# xbee_adapter.net
KiCad netlist of a schematic drawn in EAGLE
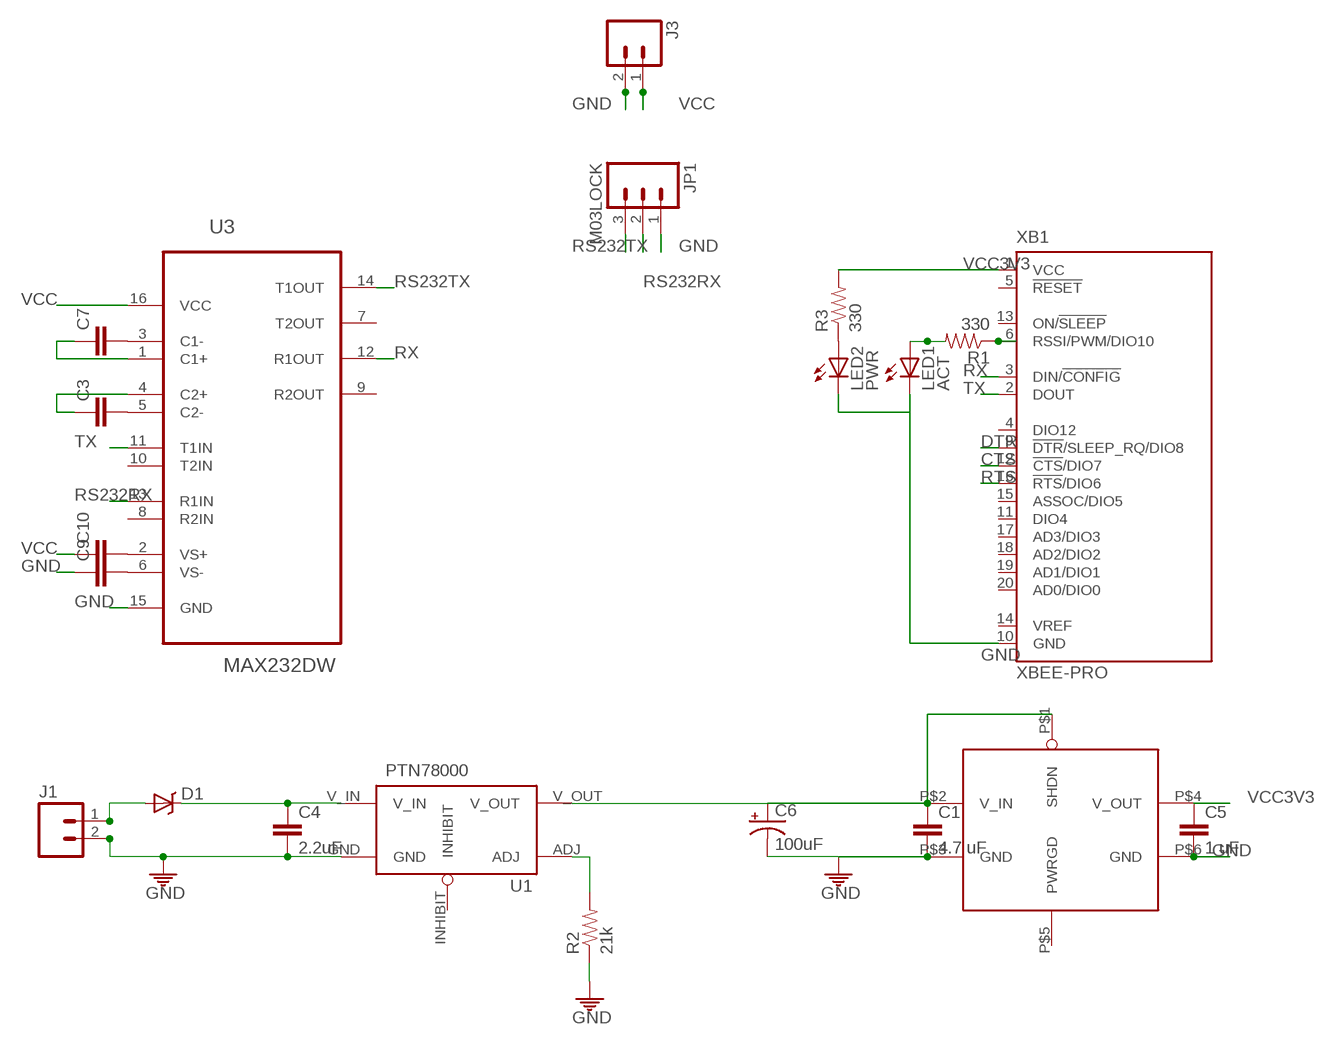
[diagram p0: schematic, sheet 1]

(export (version "E")
  (design (tool "Eeschema 10.0.6"))
  (components
    (comp (ref "C1")
      (value "4.7 uF")
      (footprint "eagle-import:1206")
      (libsource (lib "eagle-import") (part "CAP1206"))
    )
    (comp (ref "C3")
      (value "CAP1206")
      (footprint "eagle-import:1206")
      (libsource (lib "eagle-import") (part "CAP1206"))
    )
    (comp (ref "C4")
      (value "2.2uF")
      (footprint "eagle-import:1206")
      (libsource (lib "eagle-import") (part "CMPE118lib_CAP1206"))
    )
    (comp (ref "C5")
      (value "1 uF")
      (footprint "eagle-import:1206")
      (libsource (lib "eagle-import") (part "CAP1206"))
    )
    (comp (ref "C6")
      (value "100uF")
      (footprint "eagle-import:CPOL_6.6")
      (libsource (lib "eagle-import") (part "CAP_POL"))
    )
    (comp (ref "C7")
      (value "CAP1206")
      (footprint "eagle-import:1206")
      (libsource (lib "eagle-import") (part "CAP1206"))
    )
    (comp (ref "C9")
      (value "CAP1206")
      (footprint "eagle-import:1206")
      (libsource (lib "eagle-import") (part "CAP1206"))
    )
    (comp (ref "C10")
      (value "CAP1206")
      (footprint "eagle-import:1206")
      (libsource (lib "eagle-import") (part "CAP1206"))
    )
    (comp (ref "D1")
      (value "DIODE-SCHOTTKY240A")
      (footprint "eagle-import:SMA-DIODE-B240A")
      (libsource (lib "eagle-import") (part "DIODE-SCHOTTKY240A"))
    )
    (comp (ref "J1")
      (value "M023.5MM-NO_SILK")
      (footprint "eagle-import:SCREWTERMINAL-3.5MM-2-NS")
      (libsource (lib "eagle-import") (part "M023.5MM-NO_SILK"))
    )
    (comp (ref "J3")
      (value "M023.5MM-NO_SILK")
      (footprint "eagle-import:SCREWTERMINAL-3.5MM-2-NS")
      (libsource (lib "eagle-import") (part "M023.5MM-NO_SILK"))
    )
    (comp (ref "JP1")
      (value "M03LOCK")
      (footprint "eagle-import:1X03_LOCK")
      (libsource (lib "eagle-import") (part "M03LOCK"))
    )
    (comp (ref "LED1")
      (value "ACT")
      (footprint "eagle-import:LED-1206")
      (libsource (lib "eagle-import") (part "LED1206"))
    )
    (comp (ref "LED2")
      (value "PWR")
      (footprint "eagle-import:LED-1206")
      (libsource (lib "eagle-import") (part "LED1206"))
    )
    (comp (ref "R1")
      (value "330")
      (footprint "eagle-import:0805")
      (libsource (lib "eagle-import") (part "RESISTOR0805-RES"))
    )
    (comp (ref "R2")
      (value "21k")
      (footprint "eagle-import:0805")
      (libsource (lib "eagle-import") (part "CMPE118lib_RESISTOR0805-RES"))
    )
    (comp (ref "R3")
      (value "330")
      (footprint "eagle-import:0805")
      (libsource (lib "eagle-import") (part "RESISTOR0805-RES"))
    )
    (comp (ref "U$2")
      (value "MCP1826")
      (footprint "eagle-import:SOT223-5")
      (libsource (lib "eagle-import") (part "MCP1826"))
    )
    (comp (ref "U1")
      (value "PTN78000")
      (footprint "eagle-import:PTN78000")
      (libsource (lib "eagle-import") (part "PTN78000THROUGH-HOLE"))
    )
    (comp (ref "U3")
      (value "MAX232DW")
      (footprint "eagle-import:SOIC127P1030X265-16N")
      (libsource (lib "eagle-import") (part "MAX232DW"))
    )
    (comp (ref "XB1")
      (value "XBEE-PRO")
      (footprint "eagle-import:XBEE-PRO")
      (fields (field (name "MPN") "XBP24-AWI-001"))
      (libsource (lib "eagle-import") (part "XBEE-PRO"))
    )
  )
  (nets
    (net (code "1") (name "/CTS") (class "Default")
      (node (ref "XB1") (pin "12") (pinfunction "~{CTS}/DIO7_12") (pintype "bidirectional"))
    )
    (net (code "2") (name "/DTR") (class "Default")
      (node (ref "XB1") (pin "9") (pinfunction "~{DTR}/SLEEP_RQ/DIO8_9") (pintype "bidirectional"))
    )
    (net (code "3") (name "/RS232RX") (class "Default")
      (node (ref "JP1") (pin "2") (pinfunction "2_2") (pintype "passive"))
      (node (ref "U3") (pin "13") (pinfunction "R1IN_13") (pintype "input"))
    )
    (net (code "4") (name "/RS232TX") (class "Default")
      (node (ref "JP1") (pin "3") (pinfunction "3_3") (pintype "passive"))
      (node (ref "U3") (pin "14") (pinfunction "T1OUT_14") (pintype "output"))
    )
    (net (code "5") (name "/RTS") (class "Default")
      (node (ref "XB1") (pin "16") (pinfunction "~{RTS}/DIO6_16") (pintype "bidirectional"))
    )
    (net (code "6") (name "/RX") (class "Default")
      (node (ref "U3") (pin "12") (pinfunction "R1OUT_12") (pintype "output"))
      (node (ref "XB1") (pin "3") (pinfunction "DIN/~{CONFIG}_3") (pintype "input"))
    )
    (net (code "7") (name "/TX") (class "Default")
      (node (ref "U3") (pin "11") (pinfunction "T1IN_11") (pintype "input"))
      (node (ref "XB1") (pin "2") (pinfunction "DOUT_2") (pintype "output"))
    )
    (net (code "8") (name "/VCC") (class "Default")
      (node (ref "C1") (pin "1") (pinfunction "1_1") (pintype "passive"))
      (node (ref "C10") (pin "1") (pinfunction "1_1") (pintype "passive"))
      (node (ref "C6") (pin "+") (pinfunction "+_+") (pintype "passive"))
      (node (ref "J3") (pin "1") (pinfunction "2_1") (pintype "passive"))
      (node (ref "U$2") (pin "P$1") (pinfunction "SHDN_P$1") (pintype "input"))
      (node (ref "U$2") (pin "P$2") (pinfunction "V_IN_P$2") (pintype "power_in"))
      (node (ref "U1") (pin "V_OUT") (pinfunction "V_OUT_V_OUT") (pintype "output"))
      (node (ref "U3") (pin "16") (pinfunction "VCC_16") (pintype "power_in"))
    )
    (net (code "9") (name "/VCC3V3") (class "Default")
      (node (ref "C5") (pin "1") (pinfunction "1_1") (pintype "passive"))
      (node (ref "R3") (pin "2") (pinfunction "2_2") (pintype "passive"))
      (node (ref "U$2") (pin "P$4") (pinfunction "V_OUT_P$4") (pintype "output"))
      (node (ref "XB1") (pin "1") (pinfunction "VCC_1") (pintype "power_in"))
    )
    (net (code "10") (name "GND") (class "Default")
      (node (ref "C1") (pin "2") (pinfunction "2_2") (pintype "passive"))
      (node (ref "C4") (pin "2") (pinfunction "2_2") (pintype "passive"))
      (node (ref "C5") (pin "2") (pinfunction "2_2") (pintype "passive"))
      (node (ref "C6") (pin "-") (pinfunction "-_-") (pintype "passive"))
      (node (ref "C9") (pin "1") (pinfunction "1_1") (pintype "passive"))
      (node (ref "J1") (pin "2") (pinfunction "1_2") (pintype "passive"))
      (node (ref "J3") (pin "2") (pinfunction "1_2") (pintype "passive"))
      (node (ref "JP1") (pin "1") (pinfunction "1_1") (pintype "passive"))
      (node (ref "LED1") (pin "C") (pinfunction "C_C") (pintype "passive"))
      (node (ref "LED2") (pin "C") (pinfunction "C_C") (pintype "passive"))
      (node (ref "R2") (pin "1") (pinfunction "1_1") (pintype "passive"))
      (node (ref "U$2") (pin "P$3") (pinfunction "GND_P$3") (pintype "power_in"))
      (node (ref "U$2") (pin "P$6") (pinfunction "GND_P$6") (pintype "power_in"))
      (node (ref "U1") (pin "GND") (pinfunction "GND_GND") (pintype "power_in"))
      (node (ref "U3") (pin "15") (pinfunction "GND_15") (pintype "passive"))
      (node (ref "XB1") (pin "10") (pinfunction "GND_10") (pintype "power_in"))
    )
    (net (code "11") (name "Net-(C4-Pad1)") (class "Default")
      (node (ref "C4") (pin "1") (pinfunction "1_1") (pintype "passive"))
      (node (ref "D1") (pin "C") (pinfunction "C_C") (pintype "passive"))
      (node (ref "U1") (pin "V_IN") (pinfunction "V_IN_V_IN") (pintype "power_in"))
    )
    (net (code "12") (name "Net-(J1-2)") (class "Default")
      (node (ref "D1") (pin "A") (pinfunction "A_A") (pintype "passive"))
      (node (ref "J1") (pin "1") (pinfunction "2_1") (pintype "passive"))
    )
    (net (code "13") (name "Net-(LED1-PadA)") (class "Default")
      (node (ref "LED1") (pin "A") (pinfunction "A_A") (pintype "passive"))
      (node (ref "R1") (pin "2") (pinfunction "2_2") (pintype "passive"))
    )
    (net (code "14") (name "Net-(LED2-PadA)") (class "Default")
      (node (ref "LED2") (pin "A") (pinfunction "A_A") (pintype "passive"))
      (node (ref "R3") (pin "1") (pinfunction "1_1") (pintype "passive"))
    )
    (net (code "15") (name "Net-(R2-Pad2)") (class "Default")
      (node (ref "R2") (pin "2") (pinfunction "2_2") (pintype "passive"))
      (node (ref "U1") (pin "ADJ") (pinfunction "ADJ_ADJ") (pintype "input"))
    )
    (net (code "16") (name "Net-(U3-C1+)") (class "Default")
      (node (ref "C7") (pin "1") (pinfunction "1_1") (pintype "passive"))
      (node (ref "U3") (pin "1") (pinfunction "C1+_1") (pintype "passive"))
    )
    (net (code "17") (name "Net-(U3-C1-)") (class "Default")
      (node (ref "C7") (pin "2") (pinfunction "2_2") (pintype "passive"))
      (node (ref "U3") (pin "3") (pinfunction "C1-_3") (pintype "passive"))
    )
    (net (code "18") (name "Net-(U3-C2+)") (class "Default")
      (node (ref "C3") (pin "1") (pinfunction "1_1") (pintype "passive"))
      (node (ref "U3") (pin "4") (pinfunction "C2+_4") (pintype "passive"))
    )
    (net (code "19") (name "Net-(U3-C2-)") (class "Default")
      (node (ref "C3") (pin "2") (pinfunction "2_2") (pintype "passive"))
      (node (ref "U3") (pin "5") (pinfunction "C2-_5") (pintype "passive"))
    )
    (net (code "20") (name "Net-(U3-VS+)") (class "Default")
      (node (ref "C10") (pin "2") (pinfunction "2_2") (pintype "passive"))
      (node (ref "U3") (pin "2") (pinfunction "VS+_2") (pintype "power_in"))
    )
    (net (code "21") (name "Net-(U3-VS-)") (class "Default")
      (node (ref "C9") (pin "2") (pinfunction "2_2") (pintype "passive"))
      (node (ref "U3") (pin "6") (pinfunction "VS-_6") (pintype "power_in"))
    )
    (net (code "22") (name "Net-(XB1-RSSI{slash}PWM{slash}DIO10)") (class "Default")
      (node (ref "R1") (pin "1") (pinfunction "1_1") (pintype "passive"))
      (node (ref "XB1") (pin "6") (pinfunction "RSSI/PWM/DIO10_6") (pintype "output"))
    )
    (net (code "23") (name "unconnected-(U$2-PWRGD-PadP$5)") (class "Default")
      (node (ref "U$2") (pin "P$5") (pinfunction "PWRGD_P$5") (pintype "open_collector"))
    )
    (net (code "24") (name "unconnected-(U1-PadINHIBIT)") (class "Default")
      (node (ref "U1") (pin "INHIBIT") (pinfunction "INHIBIT_INHIBIT") (pintype "input"))
    )
    (net (code "25") (name "unconnected-(U3-R2IN-Pad8)") (class "Default")
      (node (ref "U3") (pin "8") (pinfunction "R2IN_8") (pintype "input"))
    )
    (net (code "26") (name "unconnected-(U3-R2OUT-Pad9)") (class "Default")
      (node (ref "U3") (pin "9") (pinfunction "R2OUT_9") (pintype "output"))
    )
    (net (code "27") (name "unconnected-(U3-T2IN-Pad10)") (class "Default")
      (node (ref "U3") (pin "10") (pinfunction "T2IN_10") (pintype "input"))
    )
    (net (code "28") (name "unconnected-(U3-T2OUT-Pad7)") (class "Default")
      (node (ref "U3") (pin "7") (pinfunction "T2OUT_7") (pintype "output"))
    )
    (net (code "29") (name "unconnected-(XB1-AD0{slash}DIO0-Pad20)") (class "Default")
      (node (ref "XB1") (pin "20") (pinfunction "AD0/DIO0_20") (pintype "bidirectional"))
    )
    (net (code "30") (name "unconnected-(XB1-AD1{slash}DIO1-Pad19)") (class "Default")
      (node (ref "XB1") (pin "19") (pinfunction "AD1/DIO1_19") (pintype "bidirectional"))
    )
    (net (code "31") (name "unconnected-(XB1-AD2{slash}DIO2-Pad18)") (class "Default")
      (node (ref "XB1") (pin "18") (pinfunction "AD2/DIO2_18") (pintype "bidirectional"))
    )
    (net (code "32") (name "unconnected-(XB1-AD3{slash}DIO3-Pad17)") (class "Default")
      (node (ref "XB1") (pin "17") (pinfunction "AD3/DIO3_17") (pintype "bidirectional"))
    )
    (net (code "33") (name "unconnected-(XB1-ASSOC{slash}DIO5-Pad15)") (class "Default")
      (node (ref "XB1") (pin "15") (pinfunction "ASSOC/DIO5_15") (pintype "bidirectional"))
    )
    (net (code "34") (name "unconnected-(XB1-DIO4-Pad11)") (class "Default")
      (node (ref "XB1") (pin "11") (pinfunction "DIO4_11") (pintype "bidirectional"))
    )
    (net (code "35") (name "unconnected-(XB1-DIO12-Pad4)") (class "Default")
      (node (ref "XB1") (pin "4") (pinfunction "DIO12_4") (pintype "bidirectional"))
    )
    (net (code "36") (name "unconnected-(XB1-ON{slash}~{SLEEP}-Pad13)") (class "Default")
      (node (ref "XB1") (pin "13") (pinfunction "ON/~{SLEEP}_13") (pintype "output"))
    )
    (net (code "37") (name "unconnected-(XB1-VREF-Pad14)") (class "Default")
      (node (ref "XB1") (pin "14") (pinfunction "VREF_14") (pintype "input"))
    )
    (net (code "38") (name "unconnected-(XB1-~{RESET}-Pad5)") (class "Default")
      (node (ref "XB1") (pin "5") (pinfunction "~{RESET}_5") (pintype "input"))
    )
  )
)
